# transducer.net
KiCad netlist of a schematic drawn in EAGLE
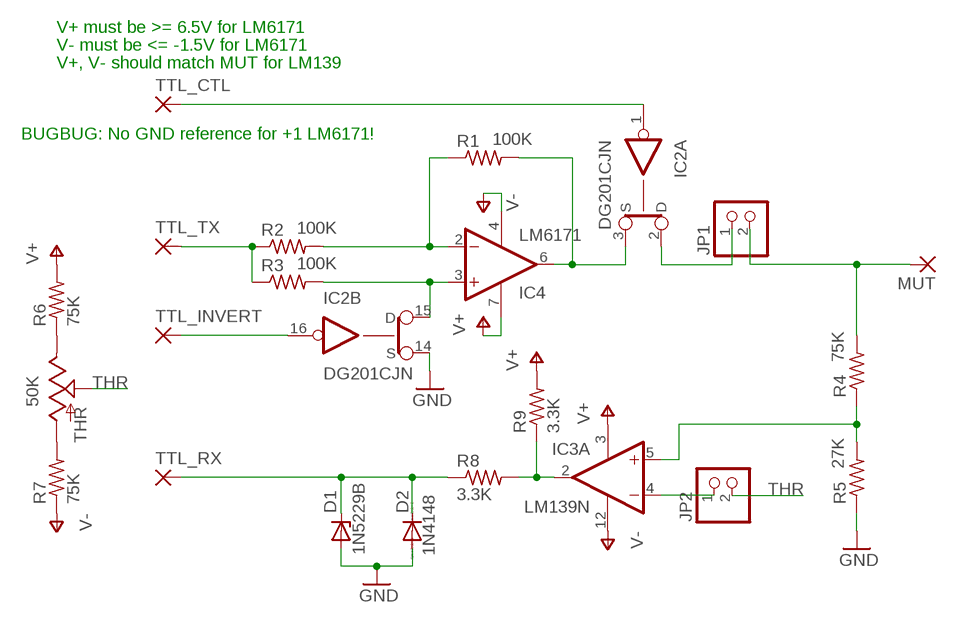
[diagram p0: schematic, sheet 1]

(export (version "E")
  (design (tool "Eeschema 10.0.6"))
  (components
    (comp (ref "D1")
      (value "1N5229B")
      (footprint "eagle-import:DO35Z10")
      (libsource (lib "eagle-import") (part "ZENER-DIODEDO35Z10"))
    )
    (comp (ref "D2")
      (value "1N4148")
      (footprint "eagle-import:DO35-10")
      (libsource (lib "eagle-import") (part "1N4148DO35-10"))
    )
    (comp (ref "IC2")
      (value "DG201CJN")
      (footprint "eagle-import:DIL16")
      (libsource (lib "eagle-import") (part "DG201CJN"))
    )
    (comp (ref "IC3")
      (value "LM139N")
      (footprint "eagle-import:DIL14")
      (libsource (lib "eagle-import") (part "LM339N"))
    )
    (comp (ref "IC4")
      (value "LM6171")
      (footprint "eagle-import:DIL08")
      (libsource (lib "eagle-import") (part "1AMP_P7+4N"))
    )
    (comp (ref "JP1")
      (value "PINHD-1X2")
      (footprint "eagle-import:1X02")
      (libsource (lib "eagle-import") (part "PINHD-1X2"))
    )
    (comp (ref "JP2")
      (value "PINHD-1X2")
      (footprint "eagle-import:1X02")
      (libsource (lib "eagle-import") (part "PINHD-1X2"))
    )
    (comp (ref "MUT")
      (value "1,6/0,9")
      (footprint "eagle-import:1,6_0,9")
      (libsource (lib "eagle-import") (part "1,6/0,9"))
    )
    (comp (ref "R1")
      (value "100K")
      (footprint "eagle-import:0207_10")
      (libsource (lib "eagle-import") (part "R-US_0207/10"))
    )
    (comp (ref "R2")
      (value "100K")
      (footprint "eagle-import:0207_10")
      (libsource (lib "eagle-import") (part "R-US_0207/10"))
    )
    (comp (ref "R3")
      (value "100K")
      (footprint "eagle-import:0207_10")
      (libsource (lib "eagle-import") (part "R-US_0207/10"))
    )
    (comp (ref "R4")
      (value "75K")
      (footprint "eagle-import:0207_10")
      (libsource (lib "eagle-import") (part "R-US_0207/10"))
    )
    (comp (ref "R5")
      (value "27K")
      (footprint "eagle-import:0207_10")
      (libsource (lib "eagle-import") (part "R-US_0207/10"))
    )
    (comp (ref "R6")
      (value "75K")
      (footprint "eagle-import:0207_10")
      (libsource (lib "eagle-import") (part "R-US_0207/10"))
    )
    (comp (ref "R7")
      (value "75K")
      (footprint "eagle-import:0207_10")
      (libsource (lib "eagle-import") (part "R-US_0207/10"))
    )
    (comp (ref "R8")
      (value "3.3K")
      (footprint "eagle-import:0207_10")
      (libsource (lib "eagle-import") (part "R-US_0207/10"))
    )
    (comp (ref "R9")
      (value "3.3K")
      (footprint "eagle-import:0207_10")
      (libsource (lib "eagle-import") (part "R-US_0207/10"))
    )
    (comp (ref "THR")
      (value "50K")
      (footprint "eagle-import:SP19L")
      (libsource (lib "eagle-import") (part "TRIM_US-S43P"))
    )
    (comp (ref "TTL_CTL")
      (value "1,6/0,9")
      (footprint "eagle-import:1,6_0,9")
      (libsource (lib "eagle-import") (part "1,6/0,9"))
    )
    (comp (ref "TTL_INVERT")
      (value "1,6/0,9")
      (footprint "eagle-import:1,6_0,9")
      (libsource (lib "eagle-import") (part "1,6/0,9"))
    )
    (comp (ref "TTL_RX")
      (value "1,6/0,9")
      (footprint "eagle-import:1,6_0,9")
      (libsource (lib "eagle-import") (part "1,6/0,9"))
    )
    (comp (ref "TTL_TX")
      (value "1,6/0,9")
      (footprint "eagle-import:1,6_0,9")
      (libsource (lib "eagle-import") (part "1,6/0,9"))
    )
  )
  (nets
    (net (code "1") (name "/THR") (class "Default")
      (node (ref "JP2") (pin "2") (pinfunction "2_2") (pintype "passive"))
      (node (ref "THR") (pin "S") (pinfunction "S_S") (pintype "passive"))
    )
    (net (code "2") (name "GND") (class "Default")
      (node (ref "D1") (pin "A") (pinfunction "A_A") (pintype "passive"))
      (node (ref "D2") (pin "A") (pinfunction "A_A") (pintype "passive"))
      (node (ref "IC2") (pin "14") (pinfunction "S_14") (pintype "bidirectional"))
      (node (ref "R5") (pin "1") (pinfunction "1_1") (pintype "passive"))
    )
    (net (code "3") (name "Net-(IC2A-D)") (class "Default")
      (node (ref "IC2") (pin "2") (pinfunction "D_2") (pintype "bidirectional"))
      (node (ref "JP1") (pin "1") (pinfunction "1_1") (pintype "passive"))
    )
    (net (code "4") (name "Net-(IC2A-IN)") (class "Default")
      (node (ref "IC2") (pin "1") (pinfunction "IN_1") (pintype "input"))
      (node (ref "TTL_CTL") (pin "1") (pinfunction "P_1") (pintype "passive"))
    )
    (net (code "5") (name "Net-(IC2A-S)") (class "Default")
      (node (ref "IC2") (pin "3") (pinfunction "S_3") (pintype "bidirectional"))
      (node (ref "IC4") (pin "6") (pinfunction "OUT_6") (pintype "output"))
      (node (ref "R1") (pin "2") (pinfunction "2_2") (pintype "passive"))
    )
    (net (code "6") (name "Net-(IC2B-D)") (class "Default")
      (node (ref "IC2") (pin "15") (pinfunction "D_15") (pintype "bidirectional"))
      (node (ref "IC4") (pin "3") (pinfunction "+IN_3") (pintype "input"))
      (node (ref "R3") (pin "2") (pinfunction "2_2") (pintype "passive"))
    )
    (net (code "7") (name "Net-(IC2B-IN)") (class "Default")
      (node (ref "IC2") (pin "16") (pinfunction "IN_16") (pintype "input"))
      (node (ref "TTL_INVERT") (pin "1") (pinfunction "P_1") (pintype "passive"))
    )
    (net (code "8") (name "Net-(IC3A-+IN)") (class "Default")
      (node (ref "IC3") (pin "5") (pinfunction "+IN_5") (pintype "input"))
      (node (ref "R4") (pin "1") (pinfunction "1_1") (pintype "passive"))
      (node (ref "R5") (pin "2") (pinfunction "2_2") (pintype "passive"))
    )
    (net (code "9") (name "Net-(IC3A--IN)") (class "Default")
      (node (ref "IC3") (pin "4") (pinfunction "-IN_4") (pintype "input"))
      (node (ref "JP2") (pin "1") (pinfunction "1_1") (pintype "passive"))
    )
    (net (code "10") (name "Net-(IC3A-OUT)") (class "Default")
      (node (ref "IC3") (pin "2") (pinfunction "OUT_2") (pintype "open_collector"))
      (node (ref "R8") (pin "2") (pinfunction "2_2") (pintype "passive"))
      (node (ref "R9") (pin "1") (pinfunction "1_1") (pintype "passive"))
    )
    (net (code "11") (name "Net-(IC4--IN)") (class "Default")
      (node (ref "IC4") (pin "2") (pinfunction "-IN_2") (pintype "input"))
      (node (ref "R1") (pin "1") (pinfunction "1_1") (pintype "passive"))
      (node (ref "R2") (pin "2") (pinfunction "2_2") (pintype "passive"))
    )
    (net (code "12") (name "Net-(MUT-P)") (class "Default")
      (node (ref "JP1") (pin "2") (pinfunction "2_2") (pintype "passive"))
      (node (ref "MUT") (pin "1") (pinfunction "P_1") (pintype "passive"))
      (node (ref "R4") (pin "2") (pinfunction "2_2") (pintype "passive"))
    )
    (net (code "13") (name "Net-(R6-Pad1)") (class "Default")
      (node (ref "R6") (pin "1") (pinfunction "1_1") (pintype "passive"))
      (node (ref "THR") (pin "E") (pinfunction "E_E") (pintype "passive"))
    )
    (net (code "14") (name "Net-(R7-Pad2)") (class "Default")
      (node (ref "R7") (pin "2") (pinfunction "2_2") (pintype "passive"))
      (node (ref "THR") (pin "A") (pinfunction "A_A") (pintype "passive"))
    )
    (net (code "15") (name "Net-(TTL_RX-P)") (class "Default")
      (node (ref "D1") (pin "C") (pinfunction "C_C") (pintype "passive"))
      (node (ref "D2") (pin "C") (pinfunction "C_C") (pintype "passive"))
      (node (ref "R8") (pin "1") (pinfunction "1_1") (pintype "passive"))
      (node (ref "TTL_RX") (pin "1") (pinfunction "P_1") (pintype "passive"))
    )
    (net (code "16") (name "Net-(TTL_TX-P)") (class "Default")
      (node (ref "R2") (pin "1") (pinfunction "1_1") (pintype "passive"))
      (node (ref "R3") (pin "1") (pinfunction "1_1") (pintype "passive"))
      (node (ref "TTL_TX") (pin "1") (pinfunction "P_1") (pintype "passive"))
    )
    (net (code "17") (name "V+") (class "Default")
      (node (ref "IC3") (pin "3") (pinfunction "V+_3") (pintype "power_in"))
      (node (ref "IC4") (pin "7") (pinfunction "V+_7") (pintype "power_in"))
      (node (ref "R6") (pin "2") (pinfunction "2_2") (pintype "passive"))
      (node (ref "R9") (pin "2") (pinfunction "2_2") (pintype "passive"))
    )
    (net (code "18") (name "V-") (class "Default")
      (node (ref "IC3") (pin "12") (pinfunction "GND_12") (pintype "power_in"))
      (node (ref "IC4") (pin "4") (pinfunction "V-_4") (pintype "power_in"))
      (node (ref "R7") (pin "1") (pinfunction "1_1") (pintype "passive"))
    )
  )
)
